# 6_Jetson_Nano_P2.net
KiCad netlist of a schematic drawn in Altium Designer
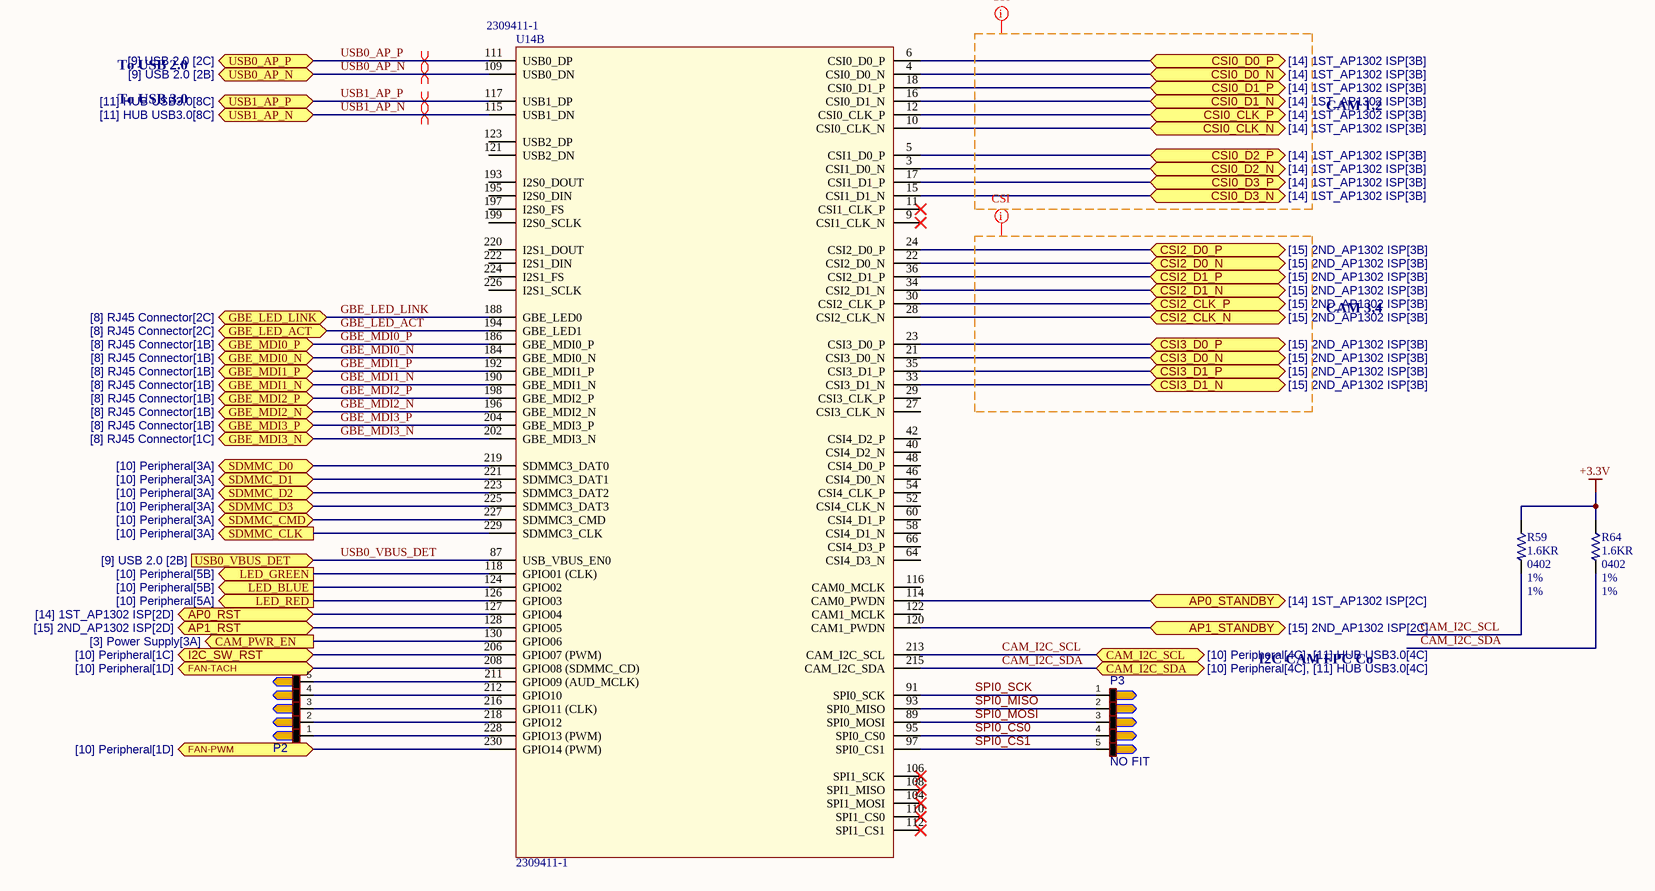
[diagram p0: [6] Jetson Nano P2.SchDoc]

(export (version "E")
  (design (tool "Eeschema 10.0.6"))
  (components
    (comp (ref "P2")
      (value "61300511021")
      (footprint "61300511021")
      (description "CONN HEADER VERT 5POS 2.54MM")
      (fields (field (name "MANUFACTURER") "Würth Elektronik GmbH"))
      (libsource (lib "") (part "WE-CN-1P-M-R5_1"))
    )
    (comp (ref "P3")
      (value "NO FIT")
      (footprint "61300511021_NO_3D")
      (description "CONN HEADER R/A 5POS 2.54MM")
      (fields
        (field (name "MANUFACTURER PART NUMBER") "61300511021")
        (field (name "MANUFACTURER") "Würth Elektronik GmbH")
      )
      (libsource (lib "3DAS_4Camera") (part "WE-CN-1P-M-R5"))
    )
    (comp (ref "R59")
      (value "1.6KR")
      (footprint "R0402M")
      (description "RES SMD 1.6K OHM 1% 1/16W 0402")
      (fields
        (field (name "CASE CODE (IMPERIAL)") "0402")
        (field (name "TOLERANCE") "1%")
        (field (name "RESISTANCE TOLERANCE") "1%")
      )
      (libsource (lib "CommonLib") (part "RES_SMD"))
    )
    (comp (ref "R64")
      (value "1.6KR")
      (footprint "R0402M")
      (description "RES SMD 1.6K OHM 1% 1/16W 0402")
      (fields
        (field (name "CASE CODE (IMPERIAL)") "0402")
        (field (name "TOLERANCE") "1%")
        (field (name "RESISTANCE TOLERANCE") "1%")
      )
      (libsource (lib "CommonLib") (part "RES_SMD"))
    )
    (comp (ref "U14")
      (value "2309411-1")
      (footprint "2309411-1")
      (description "DDR4 SODIMM 260P 8.0H STD")
      (fields
        (field (name "MANUFACTURER") "TE Connectivity")
        (field (name "SUPPLIER PART NUMBER 1") "2309411-1")
      )
      (libsource (lib "Nauvus") (part "Jetson Nano SODIMM"))
    )
  )
  (nets
    (net (code "1") (name "+3.3V") (class "Default")
      (node (ref "R59") (pin "2") (pinfunction "2_2") (pintype "passive"))
      (node (ref "R64") (pin "2") (pinfunction "2_2") (pintype "passive"))
    )
    (net (code "2") (name "/AP0_RST") (class "Default")
      (node (ref "U14") (pin "127") (pinfunction "GPIO04_127") (pintype "passive"))
    )
    (net (code "3") (name "/AP0_STANDBY") (class "Default")
      (node (ref "U14") (pin "114") (pinfunction "CAM0_PWDN_114") (pintype "passive"))
    )
    (net (code "4") (name "/AP1_RST") (class "Default")
      (node (ref "U14") (pin "128") (pinfunction "GPIO05_128") (pintype "passive"))
    )
    (net (code "5") (name "/AP1_STANDBY") (class "Default")
      (node (ref "U14") (pin "120") (pinfunction "CAM1_PWDN_120") (pintype "passive"))
    )
    (net (code "6") (name "/CAM_I2C_SCL") (class "Default")
      (node (ref "R59") (pin "1") (pinfunction "1_1") (pintype "passive"))
      (node (ref "U14") (pin "213") (pinfunction "CAM_I2C_SCL_213") (pintype "passive"))
    )
    (net (code "7") (name "/CAM_I2C_SDA") (class "Default")
      (node (ref "R64") (pin "1") (pinfunction "1_1") (pintype "passive"))
      (node (ref "U14") (pin "215") (pinfunction "CAM_I2C_SDA_215") (pintype "passive"))
    )
    (net (code "8") (name "/CAM_PWR_EN") (class "Default")
      (node (ref "U14") (pin "130") (pinfunction "GPIO06_130") (pintype "passive"))
    )
    (net (code "9") (name "/CSI0_CLK_N") (class "Default")
      (node (ref "U14") (pin "10") (pinfunction "CSI0_CLK_N_10") (pintype "passive"))
    )
    (net (code "10") (name "/CSI0_CLK_P") (class "Default")
      (node (ref "U14") (pin "12") (pinfunction "CSI0_CLK_P_12") (pintype "passive"))
    )
    (net (code "11") (name "/CSI0_D0_N") (class "Default")
      (node (ref "U14") (pin "4") (pinfunction "CSI0_D0_N_4") (pintype "passive"))
    )
    (net (code "12") (name "/CSI0_D0_P") (class "Default")
      (node (ref "U14") (pin "6") (pinfunction "CSI0_D0_P_6") (pintype "passive"))
    )
    (net (code "13") (name "/CSI0_D1_N") (class "Default")
      (node (ref "U14") (pin "16") (pinfunction "CSI0_D1_N_16") (pintype "passive"))
    )
    (net (code "14") (name "/CSI0_D1_P") (class "Default")
      (node (ref "U14") (pin "18") (pinfunction "CSI0_D1_P_18") (pintype "passive"))
    )
    (net (code "15") (name "/CSI0_D2_N") (class "Default")
      (node (ref "U14") (pin "3") (pinfunction "CSI1_D0_N_3") (pintype "passive"))
    )
    (net (code "16") (name "/CSI0_D2_P") (class "Default")
      (node (ref "U14") (pin "5") (pinfunction "CSI1_D0_P_5") (pintype "passive"))
    )
    (net (code "17") (name "/CSI0_D3_N") (class "Default")
      (node (ref "U14") (pin "15") (pinfunction "CSI1_D1_N_15") (pintype "passive"))
    )
    (net (code "18") (name "/CSI0_D3_P") (class "Default")
      (node (ref "U14") (pin "17") (pinfunction "CSI1_D1_P_17") (pintype "passive"))
    )
    (net (code "19") (name "/CSI2_CLK_N") (class "Default")
      (node (ref "U14") (pin "28") (pinfunction "CSI2_CLK_N_28") (pintype "passive"))
    )
    (net (code "20") (name "/CSI2_CLK_P") (class "Default")
      (node (ref "U14") (pin "30") (pinfunction "CSI2_CLK_P_30") (pintype "passive"))
    )
    (net (code "21") (name "/CSI2_D0_N") (class "Default")
      (node (ref "U14") (pin "22") (pinfunction "CSI2_D0_N_22") (pintype "passive"))
    )
    (net (code "22") (name "/CSI2_D0_P") (class "Default")
      (node (ref "U14") (pin "24") (pinfunction "CSI2_D0_P_24") (pintype "passive"))
    )
    (net (code "23") (name "/CSI2_D1_N") (class "Default")
      (node (ref "U14") (pin "34") (pinfunction "CSI2_D1_N_34") (pintype "passive"))
    )
    (net (code "24") (name "/CSI2_D1_P") (class "Default")
      (node (ref "U14") (pin "36") (pinfunction "CSI2_D1_P_36") (pintype "passive"))
    )
    (net (code "25") (name "/CSI3_D0_N") (class "Default")
      (node (ref "U14") (pin "21") (pinfunction "CSI3_D0_N_21") (pintype "passive"))
    )
    (net (code "26") (name "/CSI3_D0_P") (class "Default")
      (node (ref "U14") (pin "23") (pinfunction "CSI3_D0_P_23") (pintype "passive"))
    )
    (net (code "27") (name "/CSI3_D1_N") (class "Default")
      (node (ref "U14") (pin "33") (pinfunction "CSI3_D1_N_33") (pintype "passive"))
    )
    (net (code "28") (name "/CSI3_D1_P") (class "Default")
      (node (ref "U14") (pin "35") (pinfunction "CSI3_D1_P_35") (pintype "passive"))
    )
    (net (code "29") (name "/FAN-PWM") (class "Default")
      (node (ref "U14") (pin "230") (pinfunction "GPIO14_(PWM)_230") (pintype "passive"))
    )
    (net (code "30") (name "/FAN-TACH") (class "Default")
      (node (ref "U14") (pin "208") (pinfunction "GPIO08_(SDMMC_CD)_208") (pintype "passive"))
    )
    (net (code "31") (name "/GBE_LED_ACT") (class "Default")
      (node (ref "U14") (pin "194") (pinfunction "GBE_LED1_194") (pintype "passive"))
    )
    (net (code "32") (name "/GBE_LED_LINK") (class "Default")
      (node (ref "U14") (pin "188") (pinfunction "GBE_LED0_188") (pintype "passive"))
    )
    (net (code "33") (name "/GBE_MDI0_N") (class "Default")
      (node (ref "U14") (pin "184") (pinfunction "GBE_MDI0_N_184") (pintype "passive"))
    )
    (net (code "34") (name "/GBE_MDI0_P") (class "Default")
      (node (ref "U14") (pin "186") (pinfunction "GBE_MDI0_P_186") (pintype "passive"))
    )
    (net (code "35") (name "/GBE_MDI1_N") (class "Default")
      (node (ref "U14") (pin "190") (pinfunction "GBE_MDI1_N_190") (pintype "passive"))
    )
    (net (code "36") (name "/GBE_MDI1_P") (class "Default")
      (node (ref "U14") (pin "192") (pinfunction "GBE_MDI1_P_192") (pintype "passive"))
    )
    (net (code "37") (name "/GBE_MDI2_N") (class "Default")
      (node (ref "U14") (pin "196") (pinfunction "GBE_MDI2_N_196") (pintype "passive"))
    )
    (net (code "38") (name "/GBE_MDI2_P") (class "Default")
      (node (ref "U14") (pin "198") (pinfunction "GBE_MDI2_P_198") (pintype "passive"))
    )
    (net (code "39") (name "/GBE_MDI3_N") (class "Default")
      (node (ref "U14") (pin "202") (pinfunction "GBE_MDI3_N_202") (pintype "passive"))
    )
    (net (code "40") (name "/GBE_MDI3_P") (class "Default")
      (node (ref "U14") (pin "204") (pinfunction "GBE_MDI3_P_204") (pintype "passive"))
    )
    (net (code "41") (name "/I2C_SW_RST") (class "Default")
      (node (ref "U14") (pin "206") (pinfunction "GPIO07_(PWM)_206") (pintype "passive"))
    )
    (net (code "42") (name "/LED_BLUE") (class "Default")
      (node (ref "U14") (pin "124") (pinfunction "GPIO02_124") (pintype "passive"))
    )
    (net (code "43") (name "/LED_GREEN") (class "Default")
      (node (ref "U14") (pin "118") (pinfunction "GPIO01_(CLK)_118") (pintype "passive"))
    )
    (net (code "44") (name "/LED_RED") (class "Default")
      (node (ref "U14") (pin "126") (pinfunction "GPIO03_126") (pintype "passive"))
    )
    (net (code "45") (name "/SDMMC_CLK") (class "Default")
      (node (ref "U14") (pin "229") (pinfunction "SDMMC3_CLK_229") (pintype "passive"))
    )
    (net (code "46") (name "/SDMMC_CMD") (class "Default")
      (node (ref "U14") (pin "227") (pinfunction "SDMMC3_CMD_227") (pintype "passive"))
    )
    (net (code "47") (name "/SDMMC_D0") (class "Default")
      (node (ref "U14") (pin "219") (pinfunction "SDMMC3_DAT0_219") (pintype "passive"))
    )
    (net (code "48") (name "/SDMMC_D1") (class "Default")
      (node (ref "U14") (pin "221") (pinfunction "SDMMC3_DAT1_221") (pintype "passive"))
    )
    (net (code "49") (name "/SDMMC_D2") (class "Default")
      (node (ref "U14") (pin "223") (pinfunction "SDMMC3_DAT2_223") (pintype "passive"))
    )
    (net (code "50") (name "/SDMMC_D3") (class "Default")
      (node (ref "U14") (pin "225") (pinfunction "SDMMC3_DAT3_225") (pintype "passive"))
    )
    (net (code "51") (name "/SPI0_CS0") (class "Default")
      (node (ref "P3") (pin "4") (pinfunction "4_4") (pintype "passive"))
      (node (ref "U14") (pin "95") (pinfunction "SPI0_CS0_95") (pintype "passive"))
    )
    (net (code "52") (name "/SPI0_CS1") (class "Default")
      (node (ref "P3") (pin "5") (pinfunction "5_5") (pintype "passive"))
      (node (ref "U14") (pin "97") (pinfunction "SPI0_CS1_97") (pintype "passive"))
    )
    (net (code "53") (name "/SPI0_MISO") (class "Default")
      (node (ref "P3") (pin "2") (pinfunction "2_2") (pintype "passive"))
      (node (ref "U14") (pin "93") (pinfunction "SPI0_MISO_93") (pintype "passive"))
    )
    (net (code "54") (name "/SPI0_MOSI") (class "Default")
      (node (ref "P3") (pin "3") (pinfunction "3_3") (pintype "passive"))
      (node (ref "U14") (pin "89") (pinfunction "SPI0_MOSI_89") (pintype "passive"))
    )
    (net (code "55") (name "/SPI0_SCK") (class "Default")
      (node (ref "P3") (pin "1") (pinfunction "1_1") (pintype "passive"))
      (node (ref "U14") (pin "91") (pinfunction "SPI0_SCK_91") (pintype "passive"))
    )
    (net (code "56") (name "/USB0_AP_N") (class "Default")
      (node (ref "U14") (pin "109") (pinfunction "USB0_DN_109") (pintype "passive"))
    )
    (net (code "57") (name "/USB0_AP_P") (class "Default")
      (node (ref "U14") (pin "111") (pinfunction "USB0_DP_111") (pintype "passive"))
    )
    (net (code "58") (name "/USB0_VBUS_DET") (class "Default")
      (node (ref "U14") (pin "87") (pinfunction "USB_VBUS_EN0_87") (pintype "passive"))
    )
    (net (code "59") (name "/USB1_AP_N") (class "Default")
      (node (ref "U14") (pin "115") (pinfunction "USB1_DN_115") (pintype "passive"))
    )
    (net (code "60") (name "/USB1_AP_P") (class "Default")
      (node (ref "U14") (pin "117") (pinfunction "USB1_DP_117") (pintype "passive"))
    )
    (net (code "61") (name "Net-(U14B-GPIO09_(AUD_MCLK))") (class "Default")
      (node (ref "P2") (pin "5") (pinfunction "5_5") (pintype "passive"))
      (node (ref "U14") (pin "211") (pinfunction "GPIO09_(AUD_MCLK)_211") (pintype "passive"))
    )
    (net (code "62") (name "Net-(U14B-GPIO10)") (class "Default")
      (node (ref "P2") (pin "4") (pinfunction "4_4") (pintype "passive"))
      (node (ref "U14") (pin "212") (pinfunction "GPIO10_212") (pintype "passive"))
    )
    (net (code "63") (name "Net-(U14B-GPIO11_(CLK))") (class "Default")
      (node (ref "P2") (pin "3") (pinfunction "3_3") (pintype "passive"))
      (node (ref "U14") (pin "216") (pinfunction "GPIO11_(CLK)_216") (pintype "passive"))
    )
    (net (code "64") (name "Net-(U14B-GPIO12)") (class "Default")
      (node (ref "P2") (pin "2") (pinfunction "2_2") (pintype "passive"))
      (node (ref "U14") (pin "218") (pinfunction "GPIO12_218") (pintype "passive"))
    )
    (net (code "65") (name "Net-(U14B-GPIO13_(PWM))") (class "Default")
      (node (ref "P2") (pin "1") (pinfunction "1_1") (pintype "passive"))
      (node (ref "U14") (pin "228") (pinfunction "GPIO13_(PWM)_228") (pintype "passive"))
    )
    (net (code "66") (name "unconnected-(U14B-CAM0_MCLK-Pad116)") (class "Default")
      (node (ref "U14") (pin "116") (pinfunction "CAM0_MCLK_116") (pintype "passive"))
    )
    (net (code "67") (name "unconnected-(U14B-CAM1_MCLK-Pad122)") (class "Default")
      (node (ref "U14") (pin "122") (pinfunction "CAM1_MCLK_122") (pintype "passive"))
    )
    (net (code "68") (name "unconnected-(U14B-CSI1_CLK_N-Pad9)") (class "Default")
      (node (ref "U14") (pin "9") (pinfunction "CSI1_CLK_N_9") (pintype "passive+no_connect"))
    )
    (net (code "69") (name "unconnected-(U14B-CSI1_CLK_P-Pad11)") (class "Default")
      (node (ref "U14") (pin "11") (pinfunction "CSI1_CLK_P_11") (pintype "passive+no_connect"))
    )
    (net (code "70") (name "unconnected-(U14B-CSI3_CLK_N-Pad27)") (class "Default")
      (node (ref "U14") (pin "27") (pinfunction "CSI3_CLK_N_27") (pintype "passive"))
    )
    (net (code "71") (name "unconnected-(U14B-CSI3_CLK_P-Pad29)") (class "Default")
      (node (ref "U14") (pin "29") (pinfunction "CSI3_CLK_P_29") (pintype "passive"))
    )
    (net (code "72") (name "unconnected-(U14B-CSI4_CLK_N-Pad52)") (class "Default")
      (node (ref "U14") (pin "52") (pinfunction "CSI4_CLK_N_52") (pintype "passive"))
    )
    (net (code "73") (name "unconnected-(U14B-CSI4_CLK_P-Pad54)") (class "Default")
      (node (ref "U14") (pin "54") (pinfunction "CSI4_CLK_P_54") (pintype "passive"))
    )
    (net (code "74") (name "unconnected-(U14B-CSI4_D0_N-Pad46)") (class "Default")
      (node (ref "U14") (pin "46") (pinfunction "CSI4_D0_N_46") (pintype "passive"))
    )
    (net (code "75") (name "unconnected-(U14B-CSI4_D0_P-Pad48)") (class "Default")
      (node (ref "U14") (pin "48") (pinfunction "CSI4_D0_P_48") (pintype "passive"))
    )
    (net (code "76") (name "unconnected-(U14B-CSI4_D1_N-Pad58)") (class "Default")
      (node (ref "U14") (pin "58") (pinfunction "CSI4_D1_N_58") (pintype "passive"))
    )
    (net (code "77") (name "unconnected-(U14B-CSI4_D1_P-Pad60)") (class "Default")
      (node (ref "U14") (pin "60") (pinfunction "CSI4_D1_P_60") (pintype "passive"))
    )
    (net (code "78") (name "unconnected-(U14B-CSI4_D2_N-Pad40)") (class "Default")
      (node (ref "U14") (pin "40") (pinfunction "CSI4_D2_N_40") (pintype "passive"))
    )
    (net (code "79") (name "unconnected-(U14B-CSI4_D2_P-Pad42)") (class "Default")
      (node (ref "U14") (pin "42") (pinfunction "CSI4_D2_P_42") (pintype "passive"))
    )
    (net (code "80") (name "unconnected-(U14B-CSI4_D3_N-Pad64)") (class "Default")
      (node (ref "U14") (pin "64") (pinfunction "CSI4_D3_N_64") (pintype "passive"))
    )
    (net (code "81") (name "unconnected-(U14B-CSI4_D3_P-Pad66)") (class "Default")
      (node (ref "U14") (pin "66") (pinfunction "CSI4_D3_P_66") (pintype "passive"))
    )
    (net (code "82") (name "unconnected-(U14B-I2S0_DIN-Pad195)") (class "Default")
      (node (ref "U14") (pin "195") (pinfunction "I2S0_DIN_195") (pintype "passive"))
    )
    (net (code "83") (name "unconnected-(U14B-I2S0_DOUT-Pad193)") (class "Default")
      (node (ref "U14") (pin "193") (pinfunction "I2S0_DOUT_193") (pintype "passive"))
    )
    (net (code "84") (name "unconnected-(U14B-I2S0_FS-Pad197)") (class "Default")
      (node (ref "U14") (pin "197") (pinfunction "I2S0_FS_197") (pintype "passive"))
    )
    (net (code "85") (name "unconnected-(U14B-I2S0_SCLK-Pad199)") (class "Default")
      (node (ref "U14") (pin "199") (pinfunction "I2S0_SCLK_199") (pintype "passive"))
    )
    (net (code "86") (name "unconnected-(U14B-I2S1_DIN-Pad222)") (class "Default")
      (node (ref "U14") (pin "222") (pinfunction "I2S1_DIN_222") (pintype "passive"))
    )
    (net (code "87") (name "unconnected-(U14B-I2S1_DOUT-Pad220)") (class "Default")
      (node (ref "U14") (pin "220") (pinfunction "I2S1_DOUT_220") (pintype "passive"))
    )
    (net (code "88") (name "unconnected-(U14B-I2S1_FS-Pad224)") (class "Default")
      (node (ref "U14") (pin "224") (pinfunction "I2S1_FS_224") (pintype "passive"))
    )
    (net (code "89") (name "unconnected-(U14B-I2S1_SCLK-Pad226)") (class "Default")
      (node (ref "U14") (pin "226") (pinfunction "I2S1_SCLK_226") (pintype "passive"))
    )
    (net (code "90") (name "unconnected-(U14B-SPI1_CS0-Pad110)") (class "Default")
      (node (ref "U14") (pin "110") (pinfunction "SPI1_CS0_110") (pintype "passive+no_connect"))
    )
    (net (code "91") (name "unconnected-(U14B-SPI1_CS1-Pad112)") (class "Default")
      (node (ref "U14") (pin "112") (pinfunction "SPI1_CS1_112") (pintype "passive+no_connect"))
    )
    (net (code "92") (name "unconnected-(U14B-SPI1_MISO-Pad108)") (class "Default")
      (node (ref "U14") (pin "108") (pinfunction "SPI1_MISO_108") (pintype "passive+no_connect"))
    )
    (net (code "93") (name "unconnected-(U14B-SPI1_MOSI-Pad104)") (class "Default")
      (node (ref "U14") (pin "104") (pinfunction "SPI1_MOSI_104") (pintype "passive+no_connect"))
    )
    (net (code "94") (name "unconnected-(U14B-SPI1_SCK-Pad106)") (class "Default")
      (node (ref "U14") (pin "106") (pinfunction "SPI1_SCK_106") (pintype "passive+no_connect"))
    )
    (net (code "95") (name "unconnected-(U14B-USB2_DN-Pad121)") (class "Default")
      (node (ref "U14") (pin "121") (pinfunction "USB2_DN_121") (pintype "passive"))
    )
    (net (code "96") (name "unconnected-(U14B-USB2_DP-Pad123)") (class "Default")
      (node (ref "U14") (pin "123") (pinfunction "USB2_DP_123") (pintype "passive"))
    )
  )
)
